# 3_valve_front_connect.net
KiCad netlist of a schematic drawn in EAGLE
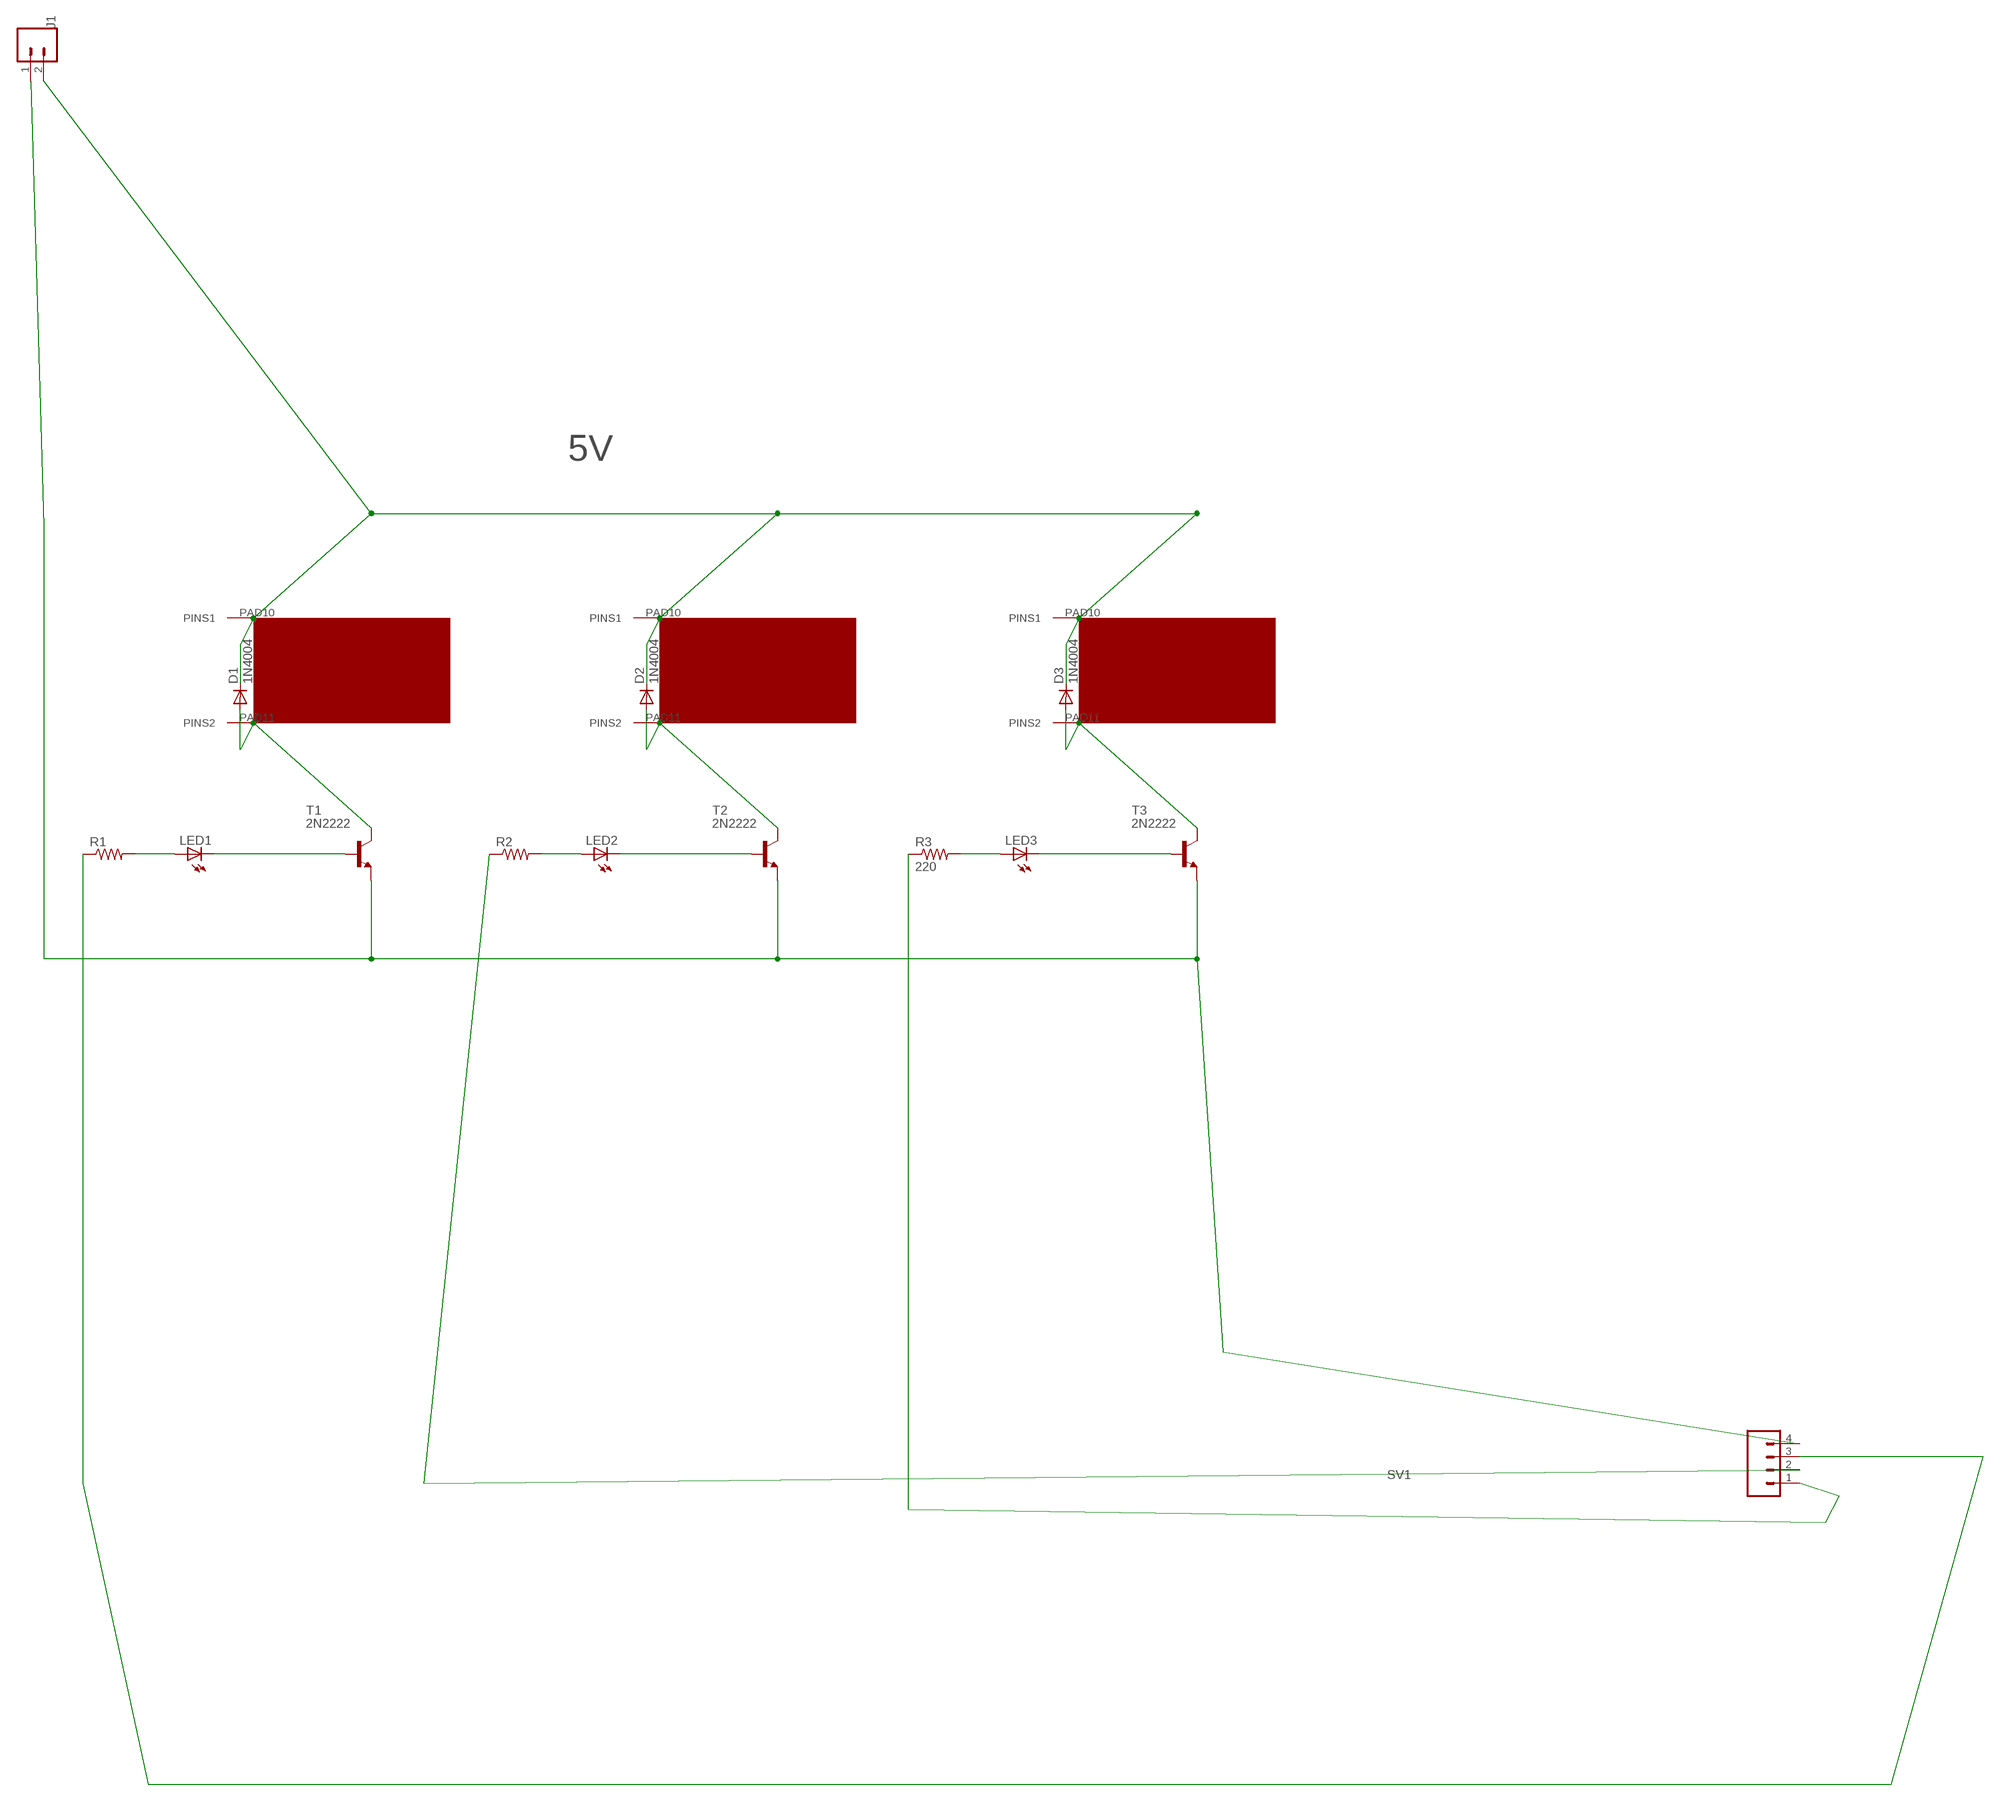
[diagram p0: schematic, sheet 1]

(export (version "E")
  (design (tool "Eeschema 10.0.6"))
  (components
    (comp (ref "D1")
      (value "1N4004")
      (footprint "eagle-import:DO41-10")
      (libsource (lib "eagle-import") (part "1N4004"))
    )
    (comp (ref "D2")
      (value "1N4004")
      (footprint "eagle-import:DO41-10")
      (libsource (lib "eagle-import") (part "1N4004"))
    )
    (comp (ref "D3")
      (value "1N4004")
      (footprint "eagle-import:DO41-10")
      (libsource (lib "eagle-import") (part "1N4004"))
    )
    (comp (ref "J1")
      (value "CONN_023.5MM")
      (footprint "eagle-import:SCREWTERMINAL-3.5MM-2")
      (libsource (lib "eagle-import") (part "CONN_023.5MM"))
    )
    (comp (ref "LED1")
      (value "LED5MM")
      (footprint "eagle-import:LED5MM")
      (libsource (lib "eagle-import") (part "LED5MM"))
    )
    (comp (ref "LED2")
      (value "LED5MM")
      (footprint "eagle-import:LED5MM")
      (libsource (lib "eagle-import") (part "LED5MM"))
    )
    (comp (ref "LED3")
      (value "LED5MM")
      (footprint "eagle-import:LED5MM")
      (libsource (lib "eagle-import") (part "LED5MM"))
    )
    (comp (ref "R1")
      (value "R-US_0207/10")
      (footprint "eagle-import:0207_10")
      (libsource (lib "eagle-import") (part "R-US_0207/10"))
    )
    (comp (ref "R2")
      (value "R-US_0207/10")
      (footprint "eagle-import:0207_10")
      (libsource (lib "eagle-import") (part "R-US_0207/10"))
    )
    (comp (ref "R3")
      (value "220")
      (footprint "eagle-import:0207_10")
      (libsource (lib "eagle-import") (part "R-US_0207/10"))
    )
    (comp (ref "SV1")
      (value "CONN_04")
      (footprint "eagle-import:1X04")
      (libsource (lib "eagle-import") (part "CONN_04"))
    )
    (comp (ref "T1")
      (value "2N2222")
      (footprint "eagle-import:TO92-EBC-OVAL")
      (libsource (lib "eagle-import") (part "2N2222"))
    )
    (comp (ref "T2")
      (value "2N2222")
      (footprint "eagle-import:TO92-EBC-OVAL")
      (libsource (lib "eagle-import") (part "2N2222"))
    )
    (comp (ref "T3")
      (value "2N2222")
      (footprint "eagle-import:TO92-EBC-OVAL")
      (libsource (lib "eagle-import") (part "2N2222"))
    )
    (comp (ref "U$1")
      (value "VALVE")
      (footprint "eagle-import:VALVTEST2")
      (libsource (lib "eagle-import") (part "VALVE"))
    )
    (comp (ref "U$2")
      (value "VALVE")
      (footprint "eagle-import:VALVTEST2")
      (libsource (lib "eagle-import") (part "VALVE"))
    )
    (comp (ref "VALVE3")
      (value "VALVE")
      (footprint "eagle-import:VALVTEST2")
      (libsource (lib "eagle-import") (part "VALVE"))
    )
  )
  (nets
    (net (code "1") (name "/5V") (class "Default")
      (node (ref "D1") (pin "C") (pinfunction "C_C") (pintype "passive"))
      (node (ref "D2") (pin "C") (pinfunction "C_C") (pintype "passive"))
      (node (ref "D3") (pin "C") (pinfunction "C_C") (pintype "passive"))
      (node (ref "J1") (pin "2") (pinfunction "2_2") (pintype "passive"))
      (node (ref "U$1") (pin "PAD10") (pinfunction "PINS1_PAD10") (pintype "bidirectional"))
      (node (ref "U$2") (pin "PAD10") (pinfunction "PINS1_PAD10") (pintype "bidirectional"))
      (node (ref "VALVE3") (pin "PAD10") (pinfunction "PINS1_PAD10") (pintype "bidirectional"))
    )
    (net (code "2") (name "Net-(J1-Pad1)") (class "Default")
      (node (ref "J1") (pin "1") (pinfunction "1_1") (pintype "passive"))
      (node (ref "SV1") (pin "4") (pinfunction "4_4") (pintype "passive"))
      (node (ref "T1") (pin "E") (pinfunction "E_E") (pintype "passive"))
      (node (ref "T2") (pin "E") (pinfunction "E_E") (pintype "passive"))
      (node (ref "T3") (pin "E") (pinfunction "E_E") (pintype "passive"))
    )
    (net (code "3") (name "Net-(LED1-C)") (class "Default")
      (node (ref "LED1") (pin "K") (pinfunction "C_K") (pintype "passive"))
      (node (ref "T1") (pin "B") (pinfunction "B_B") (pintype "passive"))
    )
    (net (code "4") (name "Net-(LED1-PadA)") (class "Default")
      (node (ref "LED1") (pin "A") (pinfunction "A_A") (pintype "passive"))
      (node (ref "R1") (pin "2") (pinfunction "2_2") (pintype "passive"))
    )
    (net (code "5") (name "Net-(LED2-C)") (class "Default")
      (node (ref "LED2") (pin "K") (pinfunction "C_K") (pintype "passive"))
      (node (ref "T2") (pin "B") (pinfunction "B_B") (pintype "passive"))
    )
    (net (code "6") (name "Net-(LED2-PadA)") (class "Default")
      (node (ref "LED2") (pin "A") (pinfunction "A_A") (pintype "passive"))
      (node (ref "R2") (pin "2") (pinfunction "2_2") (pintype "passive"))
    )
    (net (code "7") (name "Net-(LED3-C)") (class "Default")
      (node (ref "LED3") (pin "K") (pinfunction "C_K") (pintype "passive"))
      (node (ref "T3") (pin "B") (pinfunction "B_B") (pintype "passive"))
    )
    (net (code "8") (name "Net-(LED3-PadA)") (class "Default")
      (node (ref "LED3") (pin "A") (pinfunction "A_A") (pintype "passive"))
      (node (ref "R3") (pin "2") (pinfunction "2_2") (pintype "passive"))
    )
    (net (code "9") (name "Net-(R1-Pad1)") (class "Default")
      (node (ref "R1") (pin "1") (pinfunction "1_1") (pintype "passive"))
      (node (ref "SV1") (pin "3") (pinfunction "3_3") (pintype "passive"))
    )
    (net (code "10") (name "Net-(R2-Pad1)") (class "Default")
      (node (ref "R2") (pin "1") (pinfunction "1_1") (pintype "passive"))
      (node (ref "SV1") (pin "2") (pinfunction "2_2") (pintype "passive"))
    )
    (net (code "11") (name "Net-(R3-Pad1)") (class "Default")
      (node (ref "R3") (pin "1") (pinfunction "1_1") (pintype "passive"))
      (node (ref "SV1") (pin "1") (pinfunction "1_1") (pintype "passive"))
    )
    (net (code "12") (name "Net-(U$1-PINS2)") (class "Default")
      (node (ref "D1") (pin "A") (pinfunction "A_A") (pintype "passive"))
      (node (ref "T1") (pin "C") (pinfunction "C_C") (pintype "passive"))
      (node (ref "U$1") (pin "PAD11") (pinfunction "PINS2_PAD11") (pintype "bidirectional"))
    )
    (net (code "13") (name "Net-(U$2-PINS2)") (class "Default")
      (node (ref "D2") (pin "A") (pinfunction "A_A") (pintype "passive"))
      (node (ref "T2") (pin "C") (pinfunction "C_C") (pintype "passive"))
      (node (ref "U$2") (pin "PAD11") (pinfunction "PINS2_PAD11") (pintype "bidirectional"))
    )
    (net (code "14") (name "Net-(VALVE3-PINS2)") (class "Default")
      (node (ref "D3") (pin "A") (pinfunction "A_A") (pintype "passive"))
      (node (ref "T3") (pin "C") (pinfunction "C_C") (pintype "passive"))
      (node (ref "VALVE3") (pin "PAD11") (pinfunction "PINS2_PAD11") (pintype "bidirectional"))
    )
  )
)
